# untitled.net
KiCad netlist of a schematic drawn in EAGLE
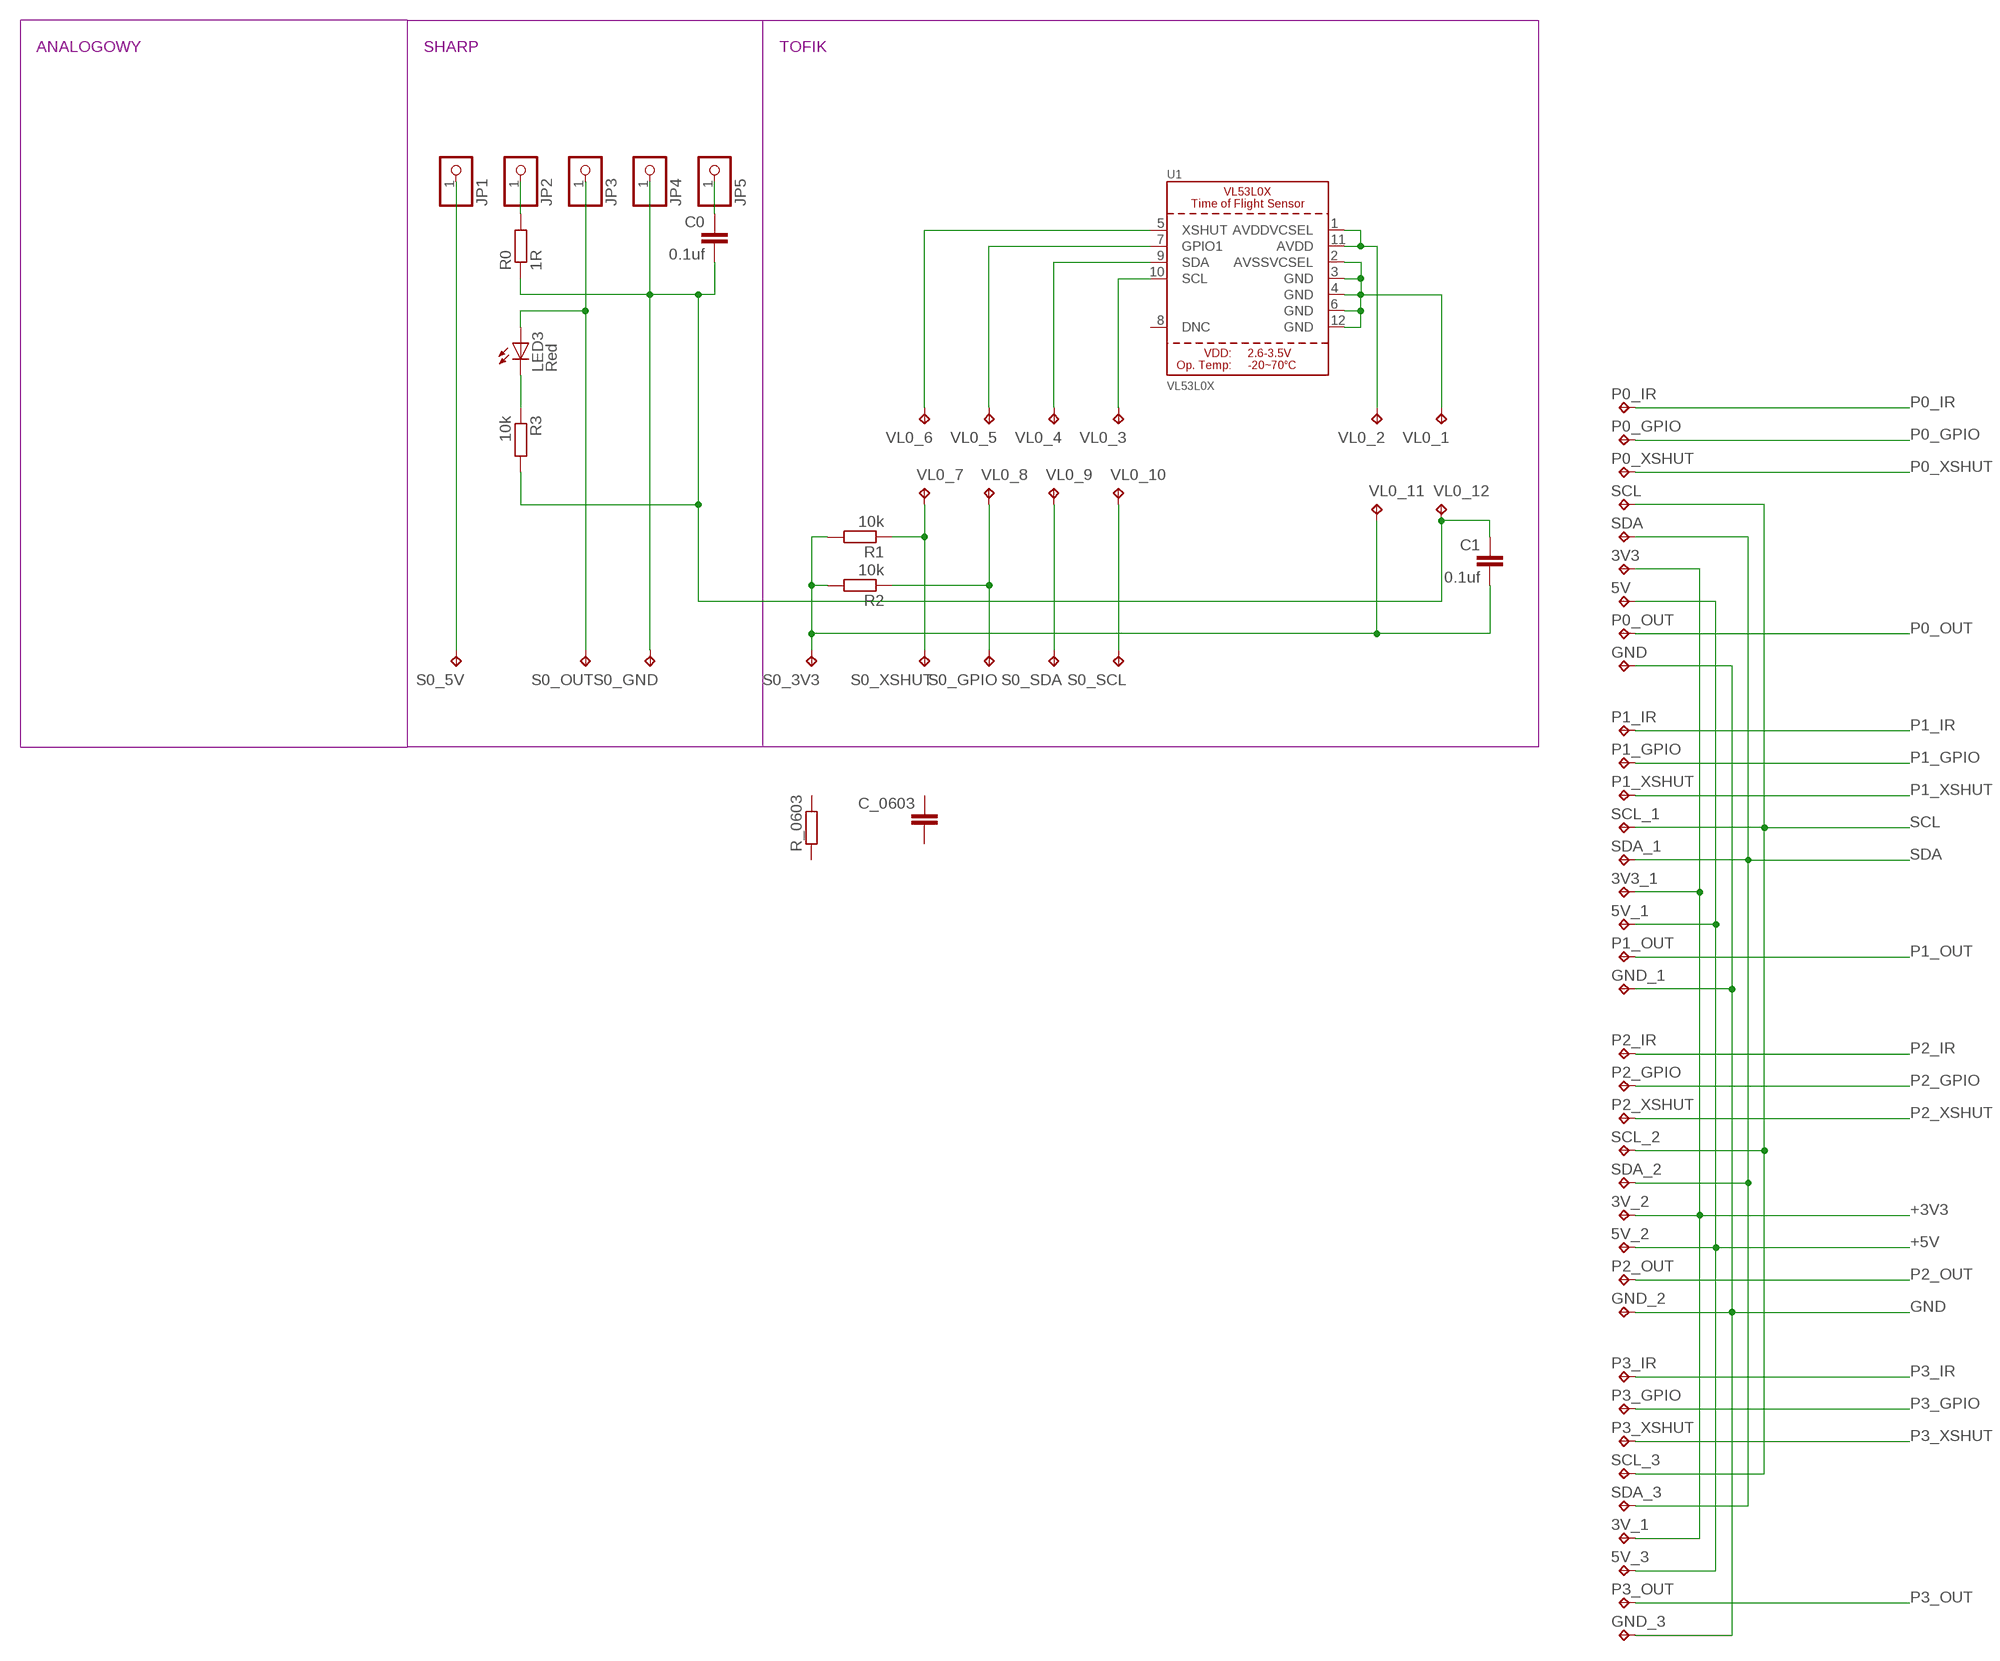
[diagram p0: schematic, sheet 1, part 1 of 2]
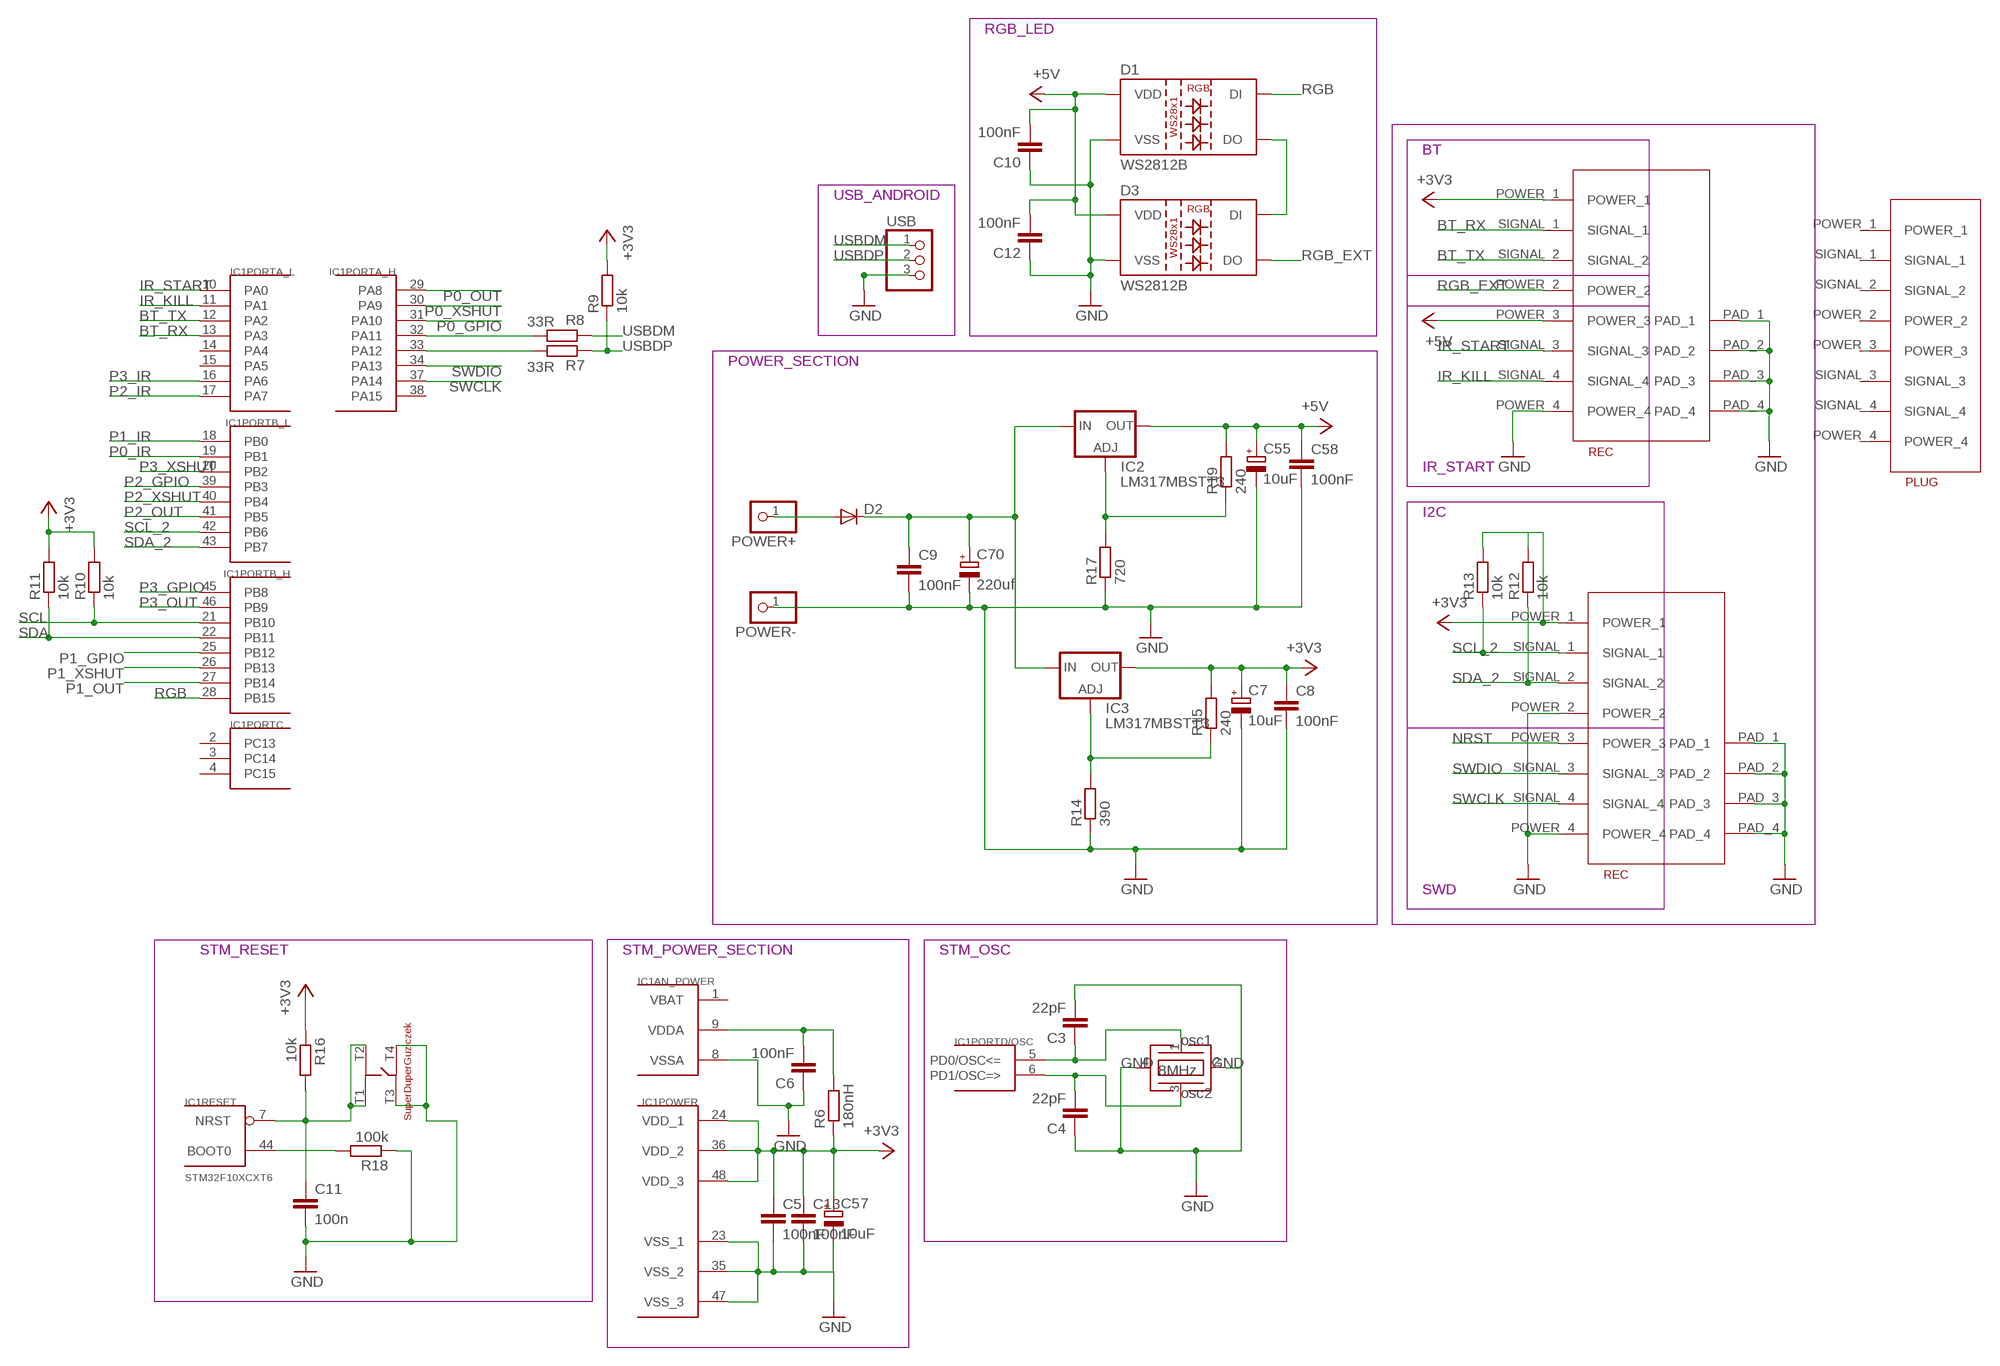
[diagram p1: schematic, sheet 1, part 2 of 2]

(export (version "E")
  (design (tool "Eeschema 10.0.6"))
  (components
    (comp (ref "3V3")
      (value "TPTP09SQ")
      (footprint "eagle-import:TP09SQ")
      (libsource (lib "eagle-import") (part "TPTP09SQ"))
    )
    (comp (ref "3V3_1")
      (value "TPTP09SQ")
      (footprint "eagle-import:TP09SQ")
      (libsource (lib "eagle-import") (part "TPTP09SQ"))
    )
    (comp (ref "3V_1")
      (value "TPTP09SQ")
      (footprint "eagle-import:TP09SQ")
      (libsource (lib "eagle-import") (part "TPTP09SQ"))
    )
    (comp (ref "3V_2")
      (value "TPTP09SQ")
      (footprint "eagle-import:TP09SQ")
      (libsource (lib "eagle-import") (part "TPTP09SQ"))
    )
    (comp (ref "5V")
      (value "TPTP09SQ")
      (footprint "eagle-import:TP09SQ")
      (libsource (lib "eagle-import") (part "TPTP09SQ"))
    )
    (comp (ref "5V_1")
      (value "TPTP09SQ")
      (footprint "eagle-import:TP09SQ")
      (libsource (lib "eagle-import") (part "TPTP09SQ"))
    )
    (comp (ref "5V_2")
      (value "TPTP09SQ")
      (footprint "eagle-import:TP09SQ")
      (libsource (lib "eagle-import") (part "TPTP09SQ"))
    )
    (comp (ref "5V_3")
      (value "TPTP09SQ")
      (footprint "eagle-import:TP09SQ")
      (libsource (lib "eagle-import") (part "TPTP09SQ"))
    )
    (comp (ref "C0")
      (value "0.1uf")
      (footprint "eagle-import:C0603")
      (libsource (lib "eagle-import") (part "C-EUC0603"))
    )
    (comp (ref "C1")
      (value "0.1uf")
      (footprint "eagle-import:C0603")
      (libsource (lib "eagle-import") (part "C-EUC0603"))
    )
    (comp (ref "C3")
      (value "22pF")
      (footprint "eagle-import:C0603")
      (libsource (lib "eagle-import") (part "C-EUC0603"))
    )
    (comp (ref "C4")
      (value "22pF")
      (footprint "eagle-import:C0603")
      (libsource (lib "eagle-import") (part "C-EUC0603"))
    )
    (comp (ref "C5")
      (value "100nF")
      (footprint "eagle-import:C0603")
      (libsource (lib "eagle-import") (part "C-EUC0603"))
    )
    (comp (ref "C6")
      (value "100nF")
      (footprint "eagle-import:C0603")
      (libsource (lib "eagle-import") (part "C-EUC0603"))
    )
    (comp (ref "C7")
      (value "10uF")
      (footprint "eagle-import:SMC_A")
      (libsource (lib "eagle-import") (part "CPOL-EUSMCA"))
    )
    (comp (ref "C8")
      (value "100nF")
      (footprint "eagle-import:C0603")
      (libsource (lib "eagle-import") (part "C-EUC0603"))
    )
    (comp (ref "C9")
      (value "100nF")
      (footprint "eagle-import:C0603")
      (libsource (lib "eagle-import") (part "C-EUC0603"))
    )
    (comp (ref "C10")
      (value "100nF")
      (footprint "eagle-import:C0603")
      (libsource (lib "eagle-import") (part "C-EUC0603"))
    )
    (comp (ref "C11")
      (value "100n")
      (footprint "eagle-import:C0603")
      (libsource (lib "eagle-import") (part "C-EUC0603"))
    )
    (comp (ref "C12")
      (value "100nF")
      (footprint "eagle-import:C0603")
      (libsource (lib "eagle-import") (part "C-EUC0603"))
    )
    (comp (ref "C13")
      (value "100nF")
      (footprint "eagle-import:C0603")
      (libsource (lib "eagle-import") (part "C-EUC0603"))
    )
    (comp (ref "C55")
      (value "10uF")
      (footprint "eagle-import:SMC_A")
      (libsource (lib "eagle-import") (part "CPOL-EUSMCA"))
    )
    (comp (ref "C57")
      (value "10uF")
      (footprint "eagle-import:SMC_A")
      (libsource (lib "eagle-import") (part "CPOL-EUSMCA"))
    )
    (comp (ref "C58")
      (value "100nF")
      (footprint "eagle-import:C0603")
      (libsource (lib "eagle-import") (part "C-EUC0603"))
    )
    (comp (ref "C70")
      (value "220uf")
      (footprint "eagle-import:150CLZ-0810")
      (libsource (lib "eagle-import") (part "CPOL-EU150CLZ-0810"))
    )
    (comp (ref "C_0603")
      (value "C-EUC0603")
      (footprint "eagle-import:C0603")
      (libsource (lib "eagle-import") (part "C-EUC0603"))
    )
    (comp (ref "D1")
      (value "WS2812B")
      (footprint "eagle-import:WS2812B")
      (libsource (lib "eagle-import") (part "WS2812B"))
    )
    (comp (ref "D2")
      (value "DIODE-DO214BA")
      (footprint "eagle-import:DO214BA")
      (libsource (lib "eagle-import") (part "DIODE-DO214BA"))
    )
    (comp (ref "D3")
      (value "WS2812B")
      (footprint "eagle-import:WS2812B")
      (libsource (lib "eagle-import") (part "WS2812B"))
    )
    (comp (ref "GND")
      (value "TPTP09SQ")
      (footprint "eagle-import:TP09SQ")
      (libsource (lib "eagle-import") (part "TPTP09SQ"))
    )
    (comp (ref "GND_1")
      (value "TPTP09SQ")
      (footprint "eagle-import:TP09SQ")
      (libsource (lib "eagle-import") (part "TPTP09SQ"))
    )
    (comp (ref "GND_2")
      (value "TPTP09SQ")
      (footprint "eagle-import:TP09SQ")
      (libsource (lib "eagle-import") (part "TPTP09SQ"))
    )
    (comp (ref "GND_3")
      (value "TPTP09SQ")
      (footprint "eagle-import:TP09SQ")
      (libsource (lib "eagle-import") (part "TPTP09SQ"))
    )
    (comp (ref "IC1")
      (value "STM32F10XCXT6")
      (footprint "eagle-import:TQFP48")
      (libsource (lib "eagle-import") (part "STM32F10XCXT6"))
    )
    (comp (ref "IC2")
      (value "LM317MBSTT3")
      (footprint "eagle-import:SOT223")
      (libsource (lib "eagle-import") (part "LM317?MBSTT3"))
    )
    (comp (ref "IC3")
      (value "LM317MBSTT3")
      (footprint "eagle-import:SOT223")
      (libsource (lib "eagle-import") (part "LM317?MBSTT3"))
    )
    (comp (ref "JP1")
      (value "PINHD-1X1")
      (footprint "eagle-import:1X01")
      (libsource (lib "eagle-import") (part "PINHD-1X1"))
    )
    (comp (ref "JP2")
      (value "PINHD-1X1")
      (footprint "eagle-import:1X01")
      (libsource (lib "eagle-import") (part "PINHD-1X1"))
    )
    (comp (ref "JP3")
      (value "PINHD-1X1")
      (footprint "eagle-import:1X01")
      (libsource (lib "eagle-import") (part "PINHD-1X1"))
    )
    (comp (ref "JP4")
      (value "PINHD-1X1")
      (footprint "eagle-import:1X01")
      (libsource (lib "eagle-import") (part "PINHD-1X1"))
    )
    (comp (ref "JP5")
      (value "PINHD-1X1")
      (footprint "eagle-import:1X01")
      (libsource (lib "eagle-import") (part "PINHD-1X1"))
    )
    (comp (ref "LED3")
      (value "Red")
      (footprint "eagle-import:SML0603")
      (libsource (lib "eagle-import") (part "LEDSML0603"))
    )
    (comp (ref "P0_GPIO")
      (value "TPTP09SQ")
      (footprint "eagle-import:TP09SQ")
      (libsource (lib "eagle-import") (part "TPTP09SQ"))
    )
    (comp (ref "P0_IR")
      (value "TPTP09SQ")
      (footprint "eagle-import:TP09SQ")
      (libsource (lib "eagle-import") (part "TPTP09SQ"))
    )
    (comp (ref "P0_OUT")
      (value "TPTP09SQ")
      (footprint "eagle-import:TP09SQ")
      (libsource (lib "eagle-import") (part "TPTP09SQ"))
    )
    (comp (ref "P0_XSHUT")
      (value "TPTP09SQ")
      (footprint "eagle-import:TP09SQ")
      (libsource (lib "eagle-import") (part "TPTP09SQ"))
    )
    (comp (ref "P1_GPIO")
      (value "TPTP09SQ")
      (footprint "eagle-import:TP09SQ")
      (libsource (lib "eagle-import") (part "TPTP09SQ"))
    )
    (comp (ref "P1_IR")
      (value "TPTP09SQ")
      (footprint "eagle-import:TP09SQ")
      (libsource (lib "eagle-import") (part "TPTP09SQ"))
    )
    (comp (ref "P1_OUT")
      (value "TPTP09SQ")
      (footprint "eagle-import:TP09SQ")
      (libsource (lib "eagle-import") (part "TPTP09SQ"))
    )
    (comp (ref "P1_XSHUT")
      (value "TPTP09SQ")
      (footprint "eagle-import:TP09SQ")
      (libsource (lib "eagle-import") (part "TPTP09SQ"))
    )
    (comp (ref "P2_GPIO")
      (value "TPTP09SQ")
      (footprint "eagle-import:TP09SQ")
      (libsource (lib "eagle-import") (part "TPTP09SQ"))
    )
    (comp (ref "P2_IR")
      (value "TPTP09SQ")
      (footprint "eagle-import:TP09SQ")
      (libsource (lib "eagle-import") (part "TPTP09SQ"))
    )
    (comp (ref "P2_OUT")
      (value "TPTP09SQ")
      (footprint "eagle-import:TP09SQ")
      (libsource (lib "eagle-import") (part "TPTP09SQ"))
    )
    (comp (ref "P2_XSHUT")
      (value "TPTP09SQ")
      (footprint "eagle-import:TP09SQ")
      (libsource (lib "eagle-import") (part "TPTP09SQ"))
    )
    (comp (ref "P3_GPIO")
      (value "TPTP09SQ")
      (footprint "eagle-import:TP09SQ")
      (libsource (lib "eagle-import") (part "TPTP09SQ"))
    )
    (comp (ref "P3_IR")
      (value "TPTP09SQ")
      (footprint "eagle-import:TP09SQ")
      (libsource (lib "eagle-import") (part "TPTP09SQ"))
    )
    (comp (ref "P3_OUT")
      (value "TPTP09SQ")
      (footprint "eagle-import:TP09SQ")
      (libsource (lib "eagle-import") (part "TPTP09SQ"))
    )
    (comp (ref "P3_XSHUT")
      (value "TPTP09SQ")
      (footprint "eagle-import:TP09SQ")
      (libsource (lib "eagle-import") (part "TPTP09SQ"))
    )
    (comp (ref "POWER+")
      (value "PINHD-1X1")
      (footprint "eagle-import:1X01")
      (libsource (lib "eagle-import") (part "PINHD-1X1"))
    )
    (comp (ref "POWER-")
      (value "PINHD-1X1")
      (footprint "eagle-import:1X01")
      (libsource (lib "eagle-import") (part "PINHD-1X1"))
    )
    (comp (ref "R0")
      (value "1R")
      (footprint "eagle-import:R0603")
      (libsource (lib "eagle-import") (part "R-EU_R0603"))
    )
    (comp (ref "R1")
      (value "10k")
      (footprint "eagle-import:R0603")
      (libsource (lib "eagle-import") (part "R-EU_R0603"))
    )
    (comp (ref "R2")
      (value "10k")
      (footprint "eagle-import:R0603")
      (libsource (lib "eagle-import") (part "R-EU_R0603"))
    )
    (comp (ref "R3")
      (value "10k")
      (footprint "eagle-import:R0603")
      (libsource (lib "eagle-import") (part "R-EU_R0603"))
    )
    (comp (ref "R6")
      (value "180nH")
      (footprint "eagle-import:R0603")
      (libsource (lib "eagle-import") (part "R-EU_R0603"))
    )
    (comp (ref "R7")
      (value "33R")
      (footprint "eagle-import:R0603")
      (libsource (lib "eagle-import") (part "R-EU_R0603"))
    )
    (comp (ref "R8")
      (value "33R")
      (footprint "eagle-import:R0603")
      (libsource (lib "eagle-import") (part "R-EU_R0603"))
    )
    (comp (ref "R9")
      (value "10k")
      (footprint "eagle-import:R0603")
      (libsource (lib "eagle-import") (part "R-EU_R0603"))
    )
    (comp (ref "R10")
      (value "10k")
      (footprint "eagle-import:R0603")
      (libsource (lib "eagle-import") (part "R-EU_R0603"))
    )
    (comp (ref "R11")
      (value "10k")
      (footprint "eagle-import:R0603")
      (libsource (lib "eagle-import") (part "R-EU_R0603"))
    )
    (comp (ref "R12")
      (value "10k")
      (footprint "eagle-import:R0603")
      (libsource (lib "eagle-import") (part "R-EU_R0603"))
    )
    (comp (ref "R13")
      (value "10k")
      (footprint "eagle-import:R0603")
      (libsource (lib "eagle-import") (part "R-EU_R0603"))
    )
    (comp (ref "R14")
      (value "390")
      (footprint "eagle-import:R0603")
      (libsource (lib "eagle-import") (part "R-EU_R0603"))
    )
    (comp (ref "R15")
      (value "240")
      (footprint "eagle-import:R0603")
      (libsource (lib "eagle-import") (part "R-EU_R0603"))
    )
    (comp (ref "R16")
      (value "10k")
      (footprint "eagle-import:R0603")
      (libsource (lib "eagle-import") (part "R-EU_R0603"))
    )
    (comp (ref "R17")
      (value "720")
      (footprint "eagle-import:R0603")
      (libsource (lib "eagle-import") (part "R-EU_R0603"))
    )
    (comp (ref "R18")
      (value "100k")
      (footprint "eagle-import:R0603")
      (libsource (lib "eagle-import") (part "R-EU_R0603"))
    )
    (comp (ref "R19")
      (value "240")
      (footprint "eagle-import:R0603")
      (libsource (lib "eagle-import") (part "R-EU_R0603"))
    )
    (comp (ref "R_0603")
      (value "R-EU_R0603")
      (footprint "eagle-import:R0603")
      (libsource (lib "eagle-import") (part "R-EU_R0603"))
    )
    (comp (ref "S0_3V3")
      (value "TPTP09SQ")
      (footprint "eagle-import:TP09SQ")
      (libsource (lib "eagle-import") (part "TPTP09SQ"))
    )
    (comp (ref "S0_5V")
      (value "TPTP09SQ")
      (footprint "eagle-import:TP09SQ")
      (libsource (lib "eagle-import") (part "TPTP09SQ"))
    )
    (comp (ref "S0_GND")
      (value "TPTP09SQ")
      (footprint "eagle-import:TP09SQ")
      (libsource (lib "eagle-import") (part "TPTP09SQ"))
    )
    (comp (ref "S0_GPIO")
      (value "TPTP09SQ")
      (footprint "eagle-import:TP09SQ")
      (libsource (lib "eagle-import") (part "TPTP09SQ"))
    )
    (comp (ref "S0_OUT")
      (value "TPTP09SQ")
      (footprint "eagle-import:TP09SQ")
      (libsource (lib "eagle-import") (part "TPTP09SQ"))
    )
    (comp (ref "S0_SCL")
      (value "TPTP09SQ")
      (footprint "eagle-import:TP09SQ")
      (libsource (lib "eagle-import") (part "TPTP09SQ"))
    )
    (comp (ref "S0_SDA")
      (value "TPTP09SQ")
      (footprint "eagle-import:TP09SQ")
      (libsource (lib "eagle-import") (part "TPTP09SQ"))
    )
    (comp (ref "S0_XSHUT")
      (value "TPTP09SQ")
      (footprint "eagle-import:TP09SQ")
      (libsource (lib "eagle-import") (part "TPTP09SQ"))
    )
    (comp (ref "SCL")
      (value "TPTP09SQ")
      (footprint "eagle-import:TP09SQ")
      (libsource (lib "eagle-import") (part "TPTP09SQ"))
    )
    (comp (ref "SCL_1")
      (value "TPTP09SQ")
      (footprint "eagle-import:TP09SQ")
      (libsource (lib "eagle-import") (part "TPTP09SQ"))
    )
    (comp (ref "SCL_2")
      (value "TPTP09SQ")
      (footprint "eagle-import:TP09SQ")
      (libsource (lib "eagle-import") (part "TPTP09SQ"))
    )
    (comp (ref "SCL_3")
      (value "TPTP09SQ")
      (footprint "eagle-import:TP09SQ")
      (libsource (lib "eagle-import") (part "TPTP09SQ"))
    )
    (comp (ref "SDA")
      (value "TPTP09SQ")
      (footprint "eagle-import:TP09SQ")
      (libsource (lib "eagle-import") (part "TPTP09SQ"))
    )
    (comp (ref "SDA_1")
      (value "TPTP09SQ")
      (footprint "eagle-import:TP09SQ")
      (libsource (lib "eagle-import") (part "TPTP09SQ"))
    )
    (comp (ref "SDA_2")
      (value "TPTP09SQ")
      (footprint "eagle-import:TP09SQ")
      (libsource (lib "eagle-import") (part "TPTP09SQ"))
    )
    (comp (ref "SDA_3")
      (value "TPTP09SQ")
      (footprint "eagle-import:TP09SQ")
      (libsource (lib "eagle-import") (part "TPTP09SQ"))
    )
    (comp (ref "U$1")
      (value "MOLEG_REC_8X0.4MM")
      (footprint "eagle-import:REC")
      (libsource (lib "eagle-import") (part "MOLEG_REC_8X0.4MM"))
    )
    (comp (ref "U$2")
      (value "MOLEX_PLUG_8X0.4MM")
      (footprint "eagle-import:PLUG")
      (libsource (lib "eagle-import") (part "MOLEX_PLUG_8X0.4MM"))
    )
    (comp (ref "U$3")
      (value "MOLEG_REC_8X0.4MM")
      (footprint "eagle-import:REC")
      (libsource (lib "eagle-import") (part "MOLEG_REC_8X0.4MM"))
    )
    (comp (ref "U$27")
      (value "SUPER_DUPER_GUZICZEK")
      (footprint "eagle-import:SUPER_DUPER_GUZICZEK")
      (libsource (lib "eagle-import") (part "SUPER_DUPER_GUZICZEK"))
    )
    (comp (ref "U$35")
      (value "8MHZ")
      (footprint "eagle-import:SMD")
      (libsource (lib "eagle-import") (part "8MHZ"))
    )
    (comp (ref "U1")
      (value "VL53L0X")
      (footprint "eagle-import:LGA12_ST")
      (libsource (lib "eagle-import") (part "VL53L0X"))
    )
    (comp (ref "USB")
      (value "PINHD-1X3")
      (footprint "eagle-import:1X03")
      (libsource (lib "eagle-import") (part "PINHD-1X3"))
    )
    (comp (ref "VL0_1")
      (value "TPTP09SQ")
      (footprint "eagle-import:TP09SQ")
      (libsource (lib "eagle-import") (part "TPTP09SQ"))
    )
    (comp (ref "VL0_2")
      (value "TPTP09SQ")
      (footprint "eagle-import:TP09SQ")
      (libsource (lib "eagle-import") (part "TPTP09SQ"))
    )
    (comp (ref "VL0_3")
      (value "TPTP09SQ")
      (footprint "eagle-import:TP09SQ")
      (libsource (lib "eagle-import") (part "TPTP09SQ"))
    )
    (comp (ref "VL0_4")
      (value "TPTP09SQ")
      (footprint "eagle-import:TP09SQ")
      (libsource (lib "eagle-import") (part "TPTP09SQ"))
    )
    (comp (ref "VL0_5")
      (value "TPTP09SQ")
      (footprint "eagle-import:TP09SQ")
      (libsource (lib "eagle-import") (part "TPTP09SQ"))
    )
    (comp (ref "VL0_6")
      (value "TPTP09SQ")
      (footprint "eagle-import:TP09SQ")
      (libsource (lib "eagle-import") (part "TPTP09SQ"))
    )
    (comp (ref "VL0_7")
      (value "TPTP09SQ")
      (footprint "eagle-import:TP09SQ")
      (libsource (lib "eagle-import") (part "TPTP09SQ"))
    )
    (comp (ref "VL0_8")
      (value "TPTP09SQ")
      (footprint "eagle-import:TP09SQ")
      (libsource (lib "eagle-import") (part "TPTP09SQ"))
    )
    (comp (ref "VL0_9")
      (value "TPTP09SQ")
      (footprint "eagle-import:TP09SQ")
      (libsource (lib "eagle-import") (part "TPTP09SQ"))
    )
    (comp (ref "VL0_10")
      (value "TPTP09SQ")
      (footprint "eagle-import:TP09SQ")
      (libsource (lib "eagle-import") (part "TPTP09SQ"))
    )
    (comp (ref "VL0_11")
      (value "TPTP09SQ")
      (footprint "eagle-import:TP09SQ")
      (libsource (lib "eagle-import") (part "TPTP09SQ"))
    )
    (comp (ref "VL0_12")
      (value "TPTP09SQ")
      (footprint "eagle-import:TP09SQ")
      (libsource (lib "eagle-import") (part "TPTP09SQ"))
    )
  )
  (nets
    (net (code "1") (name "+3V3") (class "Default")
      (node (ref "3V3") (pin "TP") (pinfunction "TP_TP") (pintype "input"))
      (node (ref "3V3_1") (pin "TP") (pinfunction "TP_TP") (pintype "input"))
      (node (ref "3V_1") (pin "TP") (pinfunction "TP_TP") (pintype "input"))
      (node (ref "3V_2") (pin "TP") (pinfunction "TP_TP") (pintype "input"))
      (node (ref "C13") (pin "1") (pinfunction "1_1") (pintype "passive"))
      (node (ref "C5") (pin "1") (pinfunction "1_1") (pintype "passive"))
      (node (ref "C57") (pin "+") (pinfunction "+_+") (pintype "passive"))
      (node (ref "C7") (pin "+") (pinfunction "+_+") (pintype "passive"))
      (node (ref "C8") (pin "1") (pinfunction "1_1") (pintype "passive"))
      (node (ref "IC1") (pin "24") (pinfunction "VDD_1_24") (pintype "power_in"))
      (node (ref "IC1") (pin "36") (pinfunction "VDD_2_36") (pintype "power_in"))
      (node (ref "IC1") (pin "48") (pinfunction "VDD_3_48") (pintype "power_in"))
      (node (ref "IC3") (pin "4") (pinfunction "OUT_4") (pintype "passive"))
      (node (ref "R10") (pin "2") (pinfunction "2_2") (pintype "passive"))
      (node (ref "R11") (pin "2") (pinfunction "2_2") (pintype "passive"))
      (node (ref "R12") (pin "2") (pinfunction "2_2") (pintype "passive"))
      (node (ref "R13") (pin "2") (pinfunction "2_2") (pintype "passive"))
      (node (ref "R15") (pin "2") (pinfunction "2_2") (pintype "passive"))
      (node (ref "R16") (pin "1") (pinfunction "1_1") (pintype "passive"))
      (node (ref "R6") (pin "1") (pinfunction "1_1") (pintype "passive"))
      (node (ref "R9") (pin "2") (pinfunction "2_2") (pintype "passive"))
      (node (ref "U$1") (pin "POWER_1") (pinfunction "POWER_1_POWER_1") (pintype "bidirectional"))
      (node (ref "U$3") (pin "POWER_1") (pinfunction "POWER_1_POWER_1") (pintype "bidirectional"))
    )
    (net (code "2") (name "+5V") (class "Default")
      (node (ref "5V") (pin "TP") (pinfunction "TP_TP") (pintype "input"))
      (node (ref "5V_1") (pin "TP") (pinfunction "TP_TP") (pintype "input"))
      (node (ref "5V_2") (pin "TP") (pinfunction "TP_TP") (pintype "input"))
      (node (ref "5V_3") (pin "TP") (pinfunction "TP_TP") (pintype "input"))
      (node (ref "C10") (pin "2") (pinfunction "2_2") (pintype "passive"))
      (node (ref "C12") (pin "2") (pinfunction "2_2") (pintype "passive"))
      (node (ref "C55") (pin "+") (pinfunction "+_+") (pintype "passive"))
      (node (ref "C58") (pin "1") (pinfunction "1_1") (pintype "passive"))
      (node (ref "D1") (pin "1") (pinfunction "VDD_1") (pintype "bidirectional"))
      (node (ref "D3") (pin "1") (pinfunction "VDD_1") (pintype "bidirectional"))
      (node (ref "IC2") (pin "4") (pinfunction "OUT_4") (pintype "passive"))
      (node (ref "R19") (pin "2") (pinfunction "2_2") (pintype "passive"))
      (node (ref "U$1") (pin "POWER_3") (pinfunction "POWER_3_POWER_3") (pintype "bidirectional"))
    )
    (net (code "3") (name "/BT_RX") (class "Default")
      (node (ref "IC1") (pin "13") (pinfunction "PA3_13") (pintype "bidirectional"))
      (node (ref "U$1") (pin "SIGNAL_1") (pinfunction "SIGNAL_1_SIGNAL_1") (pintype "bidirectional"))
    )
    (net (code "4") (name "/BT_TX") (class "Default")
      (node (ref "IC1") (pin "12") (pinfunction "PA2_12") (pintype "bidirectional"))
      (node (ref "U$1") (pin "SIGNAL_2") (pinfunction "SIGNAL_2_SIGNAL_2") (pintype "bidirectional"))
    )
    (net (code "5") (name "/IR_KILL") (class "Default")
      (node (ref "IC1") (pin "11") (pinfunction "PA1_11") (pintype "bidirectional"))
      (node (ref "U$1") (pin "SIGNAL_4") (pinfunction "SIGNAL_4_SIGNAL_4") (pintype "bidirectional"))
    )
    (net (code "6") (name "/IR_START") (class "Default")
      (node (ref "IC1") (pin "10") (pinfunction "PA0_10") (pintype "bidirectional"))
      (node (ref "U$1") (pin "SIGNAL_3") (pinfunction "SIGNAL_3_SIGNAL_3") (pintype "bidirectional"))
    )
    (net (code "7") (name "/NRST") (class "Default")
      (node (ref "C11") (pin "1") (pinfunction "1_1") (pintype "passive"))
      (node (ref "IC1") (pin "7") (pinfunction "NRST_7") (pintype "input"))
      (node (ref "R16") (pin "2") (pinfunction "2_2") (pintype "passive"))
      (node (ref "U$27") (pin "T1") (pinfunction "T1_T1") (pintype "bidirectional"))
      (node (ref "U$27") (pin "T2") (pinfunction "T2_T2") (pintype "bidirectional"))
      (node (ref "U$3") (pin "POWER_3") (pinfunction "POWER_3_POWER_3") (pintype "bidirectional"))
    )
    (net (code "8") (name "/P0_GPIO") (class "Default")
      (node (ref "IC1") (pin "31") (pinfunction "PA10_31") (pintype "bidirectional"))
      (node (ref "P0_GPIO") (pin "TP") (pinfunction "TP_TP") (pintype "input"))
    )
    (net (code "9") (name "/P0_IR") (class "Default")
      (node (ref "IC1") (pin "19") (pinfunction "PB1_19") (pintype "bidirectional"))
      (node (ref "P0_IR") (pin "TP") (pinfunction "TP_TP") (pintype "input"))
    )
    (net (code "10") (name "/P0_OUT") (class "Default")
      (node (ref "IC1") (pin "29") (pinfunction "PA8_29") (pintype "bidirectional"))
      (node (ref "P0_OUT") (pin "TP") (pinfunction "TP_TP") (pintype "input"))
    )
    (net (code "11") (name "/P0_XSHUT") (class "Default")
      (node (ref "IC1") (pin "30") (pinfunction "PA9_30") (pintype "bidirectional"))
      (node (ref "P0_XSHUT") (pin "TP") (pinfunction "TP_TP") (pintype "input"))
    )
    (net (code "12") (name "/P1_GPIO") (class "Default")
      (node (ref "IC1") (pin "25") (pinfunction "PB12_25") (pintype "bidirectional"))
      (node (ref "P1_GPIO") (pin "TP") (pinfunction "TP_TP") (pintype "input"))
    )
    (net (code "13") (name "/P1_IR") (class "Default")
      (node (ref "IC1") (pin "18") (pinfunction "PB0_18") (pintype "bidirectional"))
      (node (ref "P1_IR") (pin "TP") (pinfunction "TP_TP") (pintype "input"))
    )
    (net (code "14") (name "/P1_OUT") (class "Default")
      (node (ref "IC1") (pin "27") (pinfunction "PB14_27") (pintype "bidirectional"))
      (node (ref "P1_OUT") (pin "TP") (pinfunction "TP_TP") (pintype "input"))
    )
    (net (code "15") (name "/P1_XSHUT") (class "Default")
      (node (ref "IC1") (pin "26") (pinfunction "PB13_26") (pintype "bidirectional"))
      (node (ref "P1_XSHUT") (pin "TP") (pinfunction "TP_TP") (pintype "input"))
    )
    (net (code "16") (name "/P2_GPIO") (class "Default")
      (node (ref "IC1") (pin "39") (pinfunction "PB3_39") (pintype "bidirectional"))
      (node (ref "P2_GPIO") (pin "TP") (pinfunction "TP_TP") (pintype "input"))
    )
    (net (code "17") (name "/P2_IR") (class "Default")
      (node (ref "IC1") (pin "17") (pinfunction "PA7_17") (pintype "bidirectional"))
      (node (ref "P2_IR") (pin "TP") (pinfunction "TP_TP") (pintype "input"))
    )
    (net (code "18") (name "/P2_OUT") (class "Default")
      (node (ref "IC1") (pin "41") (pinfunction "PB5_41") (pintype "bidirectional"))
      (node (ref "P2_OUT") (pin "TP") (pinfunction "TP_TP") (pintype "input"))
    )
    (net (code "19") (name "/P2_XSHUT") (class "Default")
      (node (ref "IC1") (pin "40") (pinfunction "PB4_40") (pintype "bidirectional"))
      (node (ref "P2_XSHUT") (pin "TP") (pinfunction "TP_TP") (pintype "input"))
    )
    (net (code "20") (name "/P3_GPIO") (class "Default")
      (node (ref "IC1") (pin "45") (pinfunction "PB8_45") (pintype "bidirectional"))
      (node (ref "P3_GPIO") (pin "TP") (pinfunction "TP_TP") (pintype "input"))
    )
    (net (code "21") (name "/P3_IR") (class "Default")
      (node (ref "IC1") (pin "16") (pinfunction "PA6_16") (pintype "bidirectional"))
      (node (ref "P3_IR") (pin "TP") (pinfunction "TP_TP") (pintype "input"))
    )
    (net (code "22") (name "/P3_OUT") (class "Default")
      (node (ref "IC1") (pin "46") (pinfunction "PB9_46") (pintype "bidirectional"))
      (node (ref "P3_OUT") (pin "TP") (pinfunction "TP_TP") (pintype "input"))
    )
    (net (code "23") (name "/P3_XSHUT") (class "Default")
      (node (ref "IC1") (pin "20") (pinfunction "PB2_20") (pintype "bidirectional"))
      (node (ref "P3_XSHUT") (pin "TP") (pinfunction "TP_TP") (pintype "input"))
    )
    (net (code "24") (name "/RGB") (class "Default")
      (node (ref "D1") (pin "4") (pinfunction "DI_4") (pintype "bidirectional"))
      (node (ref "IC1") (pin "28") (pinfunction "PB15_28") (pintype "bidirectional"))
    )
    (net (code "25") (name "/RGB_EXT") (class "Default")
      (node (ref "D3") (pin "2") (pinfunction "DO_2") (pintype "bidirectional"))
      (node (ref "U$1") (pin "POWER_2") (pinfunction "POWER_2_POWER_2") (pintype "bidirectional"))
    )
    (net (code "26") (name "/SCL") (class "Default")
      (node (ref "IC1") (pin "21") (pinfunction "PB10_21") (pintype "bidirectional"))
      (node (ref "R10") (pin "1") (pinfunction "1_1") (pintype "passive"))
      (node (ref "SCL") (pin "TP") (pinfunction "TP_TP") (pintype "input"))
      (node (ref "SCL_1") (pin "TP") (pinfunction "TP_TP") (pintype "input"))
      (node (ref "SCL_2") (pin "TP") (pinfunction "TP_TP") (pintype "input"))
      (node (ref "SCL_3") (pin "TP") (pinfunction "TP_TP") (pintype "input"))
    )
    (net (code "27") (name "/SCL_2") (class "Default")
      (node (ref "IC1") (pin "42") (pinfunction "PB6_42") (pintype "bidirectional"))
      (node (ref "R13") (pin "1") (pinfunction "1_1") (pintype "passive"))
      (node (ref "U$3") (pin "SIGNAL_1") (pinfunction "SIGNAL_1_SIGNAL_1") (pintype "bidirectional"))
    )
    (net (code "28") (name "/SDA") (class "Default")
      (node (ref "IC1") (pin "22") (pinfunction "PB11_22") (pintype "bidirectional"))
      (node (ref "R11") (pin "1") (pinfunction "1_1") (pintype "passive"))
      (node (ref "SDA") (pin "TP") (pinfunction "TP_TP") (pintype "input"))
      (node (ref "SDA_1") (pin "TP") (pinfunction "TP_TP") (pintype "input"))
      (node (ref "SDA_2") (pin "TP") (pinfunction "TP_TP") (pintype "input"))
      (node (ref "SDA_3") (pin "TP") (pinfunction "TP_TP") (pintype "input"))
    )
    (net (code "29") (name "/SDA_2") (class "Default")
      (node (ref "IC1") (pin "43") (pinfunction "PB7_43") (pintype "bidirectional"))
      (node (ref "R12") (pin "1") (pinfunction "1_1") (pintype "passive"))
      (node (ref "U$3") (pin "SIGNAL_2") (pinfunction "SIGNAL_2_SIGNAL_2") (pintype "bidirectional"))
    )
    (net (code "30") (name "/SWCLK") (class "Default")
      (node (ref "IC1") (pin "37") (pinfunction "PA14_37") (pintype "bidirectional"))
      (node (ref "U$3") (pin "SIGNAL_4") (pinfunction "SIGNAL_4_SIGNAL_4") (pintype "bidirectional"))
    )
    (net (code "31") (name "/SWDIO") (class "Default")
      (node (ref "IC1") (pin "34") (pinfunction "PA13_34") (pintype "bidirectional"))
      (node (ref "U$3") (pin "SIGNAL_3") (pinfunction "SIGNAL_3_SIGNAL_3") (pintype "bidirectional"))
    )
    (net (code "32") (name "/USBDM") (class "Default")
      (node (ref "R8") (pin "1") (pinfunction "1_1") (pintype "passive"))
      (node (ref "USB") (pin "1") (pinfunction "1_1") (pintype "passive"))
    )
    (net (code "33") (name "/USBDP") (class "Default")
      (node (ref "R7") (pin "1") (pinfunction "1_1") (pintype "passive"))
      (node (ref "R9") (pin "1") (pinfunction "1_1") (pintype "passive"))
      (node (ref "USB") (pin "2") (pinfunction "2_2") (pintype "passive"))
    )
    (net (code "34") (name "/VBAT") (class "Default")
      (node (ref "IC1") (pin "1") (pinfunction "VBAT_1") (pintype "power_in"))
    )
    (net (code "35") (name "GND") (class "Default")
      (node (ref "C10") (pin "1") (pinfunction "1_1") (pintype "passive"))
      (node (ref "C11") (pin "2") (pinfunction "2_2") (pintype "passive"))
      (node (ref "C12") (pin "1") (pinfunction "1_1") (pintype "passive"))
      (node (ref "C13") (pin "2") (pinfunction "2_2") (pintype "passive"))
      (node (ref "C3") (pin "2") (pinfunction "2_2") (pintype "passive"))
      (node (ref "C4") (pin "1") (pinfunction "1_1") (pintype "passive"))
      (node (ref "C5") (pin "2") (pinfunction "2_2") (pintype "passive"))
      (node (ref "C55") (pin "-") (pinfunction "-_-") (pintype "passive"))
      (node (ref "C57") (pin "-") (pinfunction "-_-") (pintype "passive"))
      (node (ref "C58") (pin "2") (pinfunction "2_2") (pintype "passive"))
      (node (ref "C6") (pin "1") (pinfunction "1_1") (pintype "passive"))
      (node (ref "C7") (pin "-") (pinfunction "-_-") (pintype "passive"))
      (node (ref "C70") (pin "-") (pinfunction "-_-") (pintype "passive"))
      (node (ref "C8") (pin "2") (pinfunction "2_2") (pintype "passive"))
      (node (ref "C9") (pin "2") (pinfunction "2_2") (pintype "passive"))
      (node (ref "D1") (pin "3") (pinfunction "VSS_3") (pintype "bidirectional"))
      (node (ref "D3") (pin "3") (pinfunction "VSS_3") (pintype "bidirectional"))
      (node (ref "GND") (pin "TP") (pinfunction "TP_TP") (pintype "input"))
      (node (ref "GND_1") (pin "TP") (pinfunction "TP_TP") (pintype "input"))
      (node (ref "GND_2") (pin "TP") (pinfunction "TP_TP") (pintype "input"))
      (node (ref "GND_3") (pin "TP") (pinfunction "TP_TP") (pintype "input"))
      (node (ref "IC1") (pin "23") (pinfunction "VSS_1_23") (pintype "power_in"))
      (node (ref "IC1") (pin "35") (pinfunction "VSS_2_35") (pintype "power_in"))
      (node (ref "IC1") (pin "47") (pinfunction "VSS_3_47") (pintype "power_in"))
      (node (ref "IC1") (pin "8") (pinfunction "VSSA_8") (pintype "power_in"))
      (node (ref "POWER-") (pin "1") (pinfunction "1_1") (pintype "passive"))
      (node (ref "R14") (pin "1") (pinfunction "1_1") (pintype "passive"))
      (node (ref "R17") (pin "1") (pinfunction "1_1") (pintype "passive"))
      (node (ref "R18") (pin "1") (pinfunction "1_1") (pintype "passive"))
      (node (ref "U$1") (pin "PAD_1") (pinfunction "PAD_1_PAD_1") (pintype "bidirectional"))
      (node (ref "U$1") (pin "PAD_2") (pinfunction "PAD_2_PAD_2") (pintype "bidirectional"))
      (node (ref "U$1") (pin "PAD_3") (pinfunction "PAD_3_PAD_3") (pintype "bidirectional"))
      (node (ref "U$1") (pin "PAD_4") (pinfunction "PAD_4_PAD_4") (pintype "bidirectional"))
      (node (ref "U$1") (pin "POWER_4") (pinfunction "POWER_4_POWER_4") (pintype "bidirectional"))
      (node (ref "U$27") (pin "T3") (pinfunction "T3_T3") (pintype "bidirectional"))
      (node (ref "U$27") (pin "T4") (pinfunction "T4_T4") (pintype "bidirectional"))
      (node (ref "U$3") (pin "PAD_1") (pinfunction "PAD_1_PAD_1") (pintype "bidirectional"))
      (node (ref "U$3") (pin "PAD_2") (pinfunction "PAD_2_PAD_2") (pintype "bidirectional"))
      (node (ref "U$3") (pin "PAD_3") (pinfunction "PAD_3_PAD_3") (pintype "bidirectional"))
      (node (ref "U$3") (pin "PAD_4") (pinfunction "PAD_4_PAD_4") (pintype "bidirectional"))
      (node (ref "U$3") (pin "POWER_2") (pinfunction "POWER_2_POWER_2") (pintype "bidirectional"))
      (node (ref "U$3") (pin "POWER_4") (pinfunction "POWER_4_POWER_4") (pintype "bidirectional"))
      (node (ref "U$35") (pin "2") (pinfunction "GND2_2") (pintype "bidirectional"))
      (node (ref "U$35") (pin "4") (pinfunction "GND1_4") (pintype "bidirectional"))
      (node (ref "USB") (pin "3") (pinfunction "3_3") (pintype "passive"))
    )
    (net (code "36") (name "Net-(C0-Pad1)") (class "Default")
      (node (ref "C0") (pin "1") (pinfunction "1_1") (pintype "passive"))
      (node (ref "JP5") (pin "1") (pinfunction "1_1") (pintype "passive"))
    )
    (net (code "37") (name "Net-(C0-Pad2)") (class "Default")
      (node (ref "C0") (pin "2") (pinfunction "2_2") (pintype "passive"))
      (node (ref "C1") (pin "1") (pinfunction "1_1") (pintype "passive"))
      (node (ref "JP4") (pin "1") (pinfunction "1_1") (pintype "passive"))
      (node (ref "R0") (pin "1") (pinfunction "1_1") (pintype "passive"))
      (node (ref "R3") (pin "2") (pinfunction "2_2") (pintype "passive"))
      (node (ref "S0_GND") (pin "TP") (pinfunction "TP_TP") (pintype "input"))
      (node (ref "VL0_12") (pin "TP") (pinfunction "TP_TP") (pintype "input"))
    )
    (net (code "38") (name "Net-(C1-Pad2)") (class "Default")
      (node (ref "C1") (pin "2") (pinfunction "2_2") (pintype "passive"))
      (node (ref "R1") (pin "2") (pinfunction "2_2") (pintype "passive"))
      (node (ref "R2") (pin "2") (pinfunction "2_2") (pintype "passive"))
      (node (ref "S0_3V3") (pin "TP") (pinfunction "TP_TP") (pintype "input"))
      (node (ref "VL0_11") (pin "TP") (pinfunction "TP_TP") (pintype "input"))
    )
    (net (code "39") (name "Net-(D1-DO)") (class "Default")
      (node (ref "D1") (pin "2") (pinfunction "DO_2") (pintype "bidirectional"))
      (node (ref "D3") (pin "4") (pinfunction "DI_4") (pintype "bidirectional"))
    )
    (net (code "40") (name "Net-(D2-PadA)") (class "Default")
      (node (ref "D2") (pin "A") (pinfunction "A_A") (pintype "passive"))
      (node (ref "POWER+") (pin "1") (pinfunction "1_1") (pintype "passive"))
    )
    (net (code "41") (name "Net-(IC1A-VDDA)") (class "Default")
      (node (ref "C6") (pin "2") (pinfunction "2_2") (pintype "passive"))
      (node (ref "IC1") (pin "9") (pinfunction "VDDA_9") (pintype "power_in"))
      (node (ref "R6") (pin "2") (pinfunction "2_2") (pintype "passive"))
    )
    (net (code "42") (name "Net-(IC1B-PA11)") (class "Default")
      (node (ref "IC1") (pin "32") (pinfunction "PA11_32") (pintype "bidirectional"))
      (node (ref "R8") (pin "2") (pinfunction "2_2") (pintype "passive"))
    )
    (net (code "43") (name "Net-(IC1B-PA12)") (class "Default")
      (node (ref "IC1") (pin "33") (pinfunction "PA12_33") (pintype "bidirectional"))
      (node (ref "R7") (pin "2") (pinfunction "2_2") (pintype "passive"))
    )
    (net (code "44") (name "Net-(IC1G-PD0{slash}OSC<=)") (class "Default")
      (node (ref "C3") (pin "1") (pinfunction "1_1") (pintype "passive"))
      (node (ref "IC1") (pin "5") (pinfunction "PD0/OSC<=_5") (pintype "bidirectional"))
      (node (ref "U$35") (pin "1") (pinfunction "1_1") (pintype "bidirectional"))
    )
    (net (code "45") (name "Net-(IC1G-PD1{slash}OSC=>)") (class "Default")
      (node (ref "C4") (pin "2") (pinfunction "2_2") (pintype "passive"))
      (node (ref "IC1") (pin "6") (pinfunction "PD1/OSC=>_6") (pintype "bidirectional"))
      (node (ref "U$35") (pin "3") (pinfunction "2_3") (pintype "bidirectional"))
    )
    (net (code "46") (name "Net-(IC1I-BOOT0)") (class "Default")
      (node (ref "IC1") (pin "44") (pinfunction "BOOT0_44") (pintype "input"))
      (node (ref "R18") (pin "2") (pinfunction "2_2") (pintype "passive"))
    )
    (net (code "47") (name "Net-(IC2-ADJ)") (class "Default")
      (node (ref "IC2") (pin "1") (pinfunction "ADJ_1") (pintype "input"))
      (node (ref "R17") (pin "2") (pinfunction "2_2") (pintype "passive"))
      (node (ref "R19") (pin "1") (pinfunction "1_1") (pintype "passive"))
    )
    (net (code "48") (name "Net-(IC2-IN)") (class "Default")
      (node (ref "C70") (pin "+") (pinfunction "+_+") (pintype "passive"))
      (node (ref "C9") (pin "1") (pinfunction "1_1") (pintype "passive"))
      (node (ref "D2") (pin "C") (pinfunction "C_C") (pintype "passive"))
      (node (ref "IC2") (pin "3") (pinfunction "IN_3") (pintype "input"))
      (node (ref "IC3") (pin "3") (pinfunction "IN_3") (pintype "input"))
    )
    (net (code "49") (name "Net-(IC3-ADJ)") (class "Default")
      (node (ref "IC3") (pin "1") (pinfunction "ADJ_1") (pintype "input"))
      (node (ref "R14") (pin "2") (pinfunction "2_2") (pintype "passive"))
      (node (ref "R15") (pin "1") (pinfunction "1_1") (pintype "passive"))
    )
    (net (code "50") (name "Net-(JP1-Pad1)") (class "Default")
      (node (ref "JP1") (pin "1") (pinfunction "1_1") (pintype "passive"))
      (node (ref "S0_5V") (pin "TP") (pinfunction "TP_TP") (pintype "input"))
    )
    (net (code "51") (name "Net-(JP2-Pad1)") (class "Default")
      (node (ref "JP2") (pin "1") (pinfunction "1_1") (pintype "passive"))
      (node (ref "R0") (pin "2") (pinfunction "2_2") (pintype "passive"))
    )
    (net (code "52") (name "Net-(JP3-Pad1)") (class "Default")
      (node (ref "JP3") (pin "1") (pinfunction "1_1") (pintype "passive"))
      (node (ref "LED3") (pin "A") (pinfunction "A_A") (pintype "passive"))
      (node (ref "S0_OUT") (pin "TP") (pinfunction "TP_TP") (pintype "input"))
    )
    (net (code "53") (name "Net-(LED3-PadC)") (class "Default")
      (node (ref "LED3") (pin "C") (pinfunction "C_C") (pintype "passive"))
      (node (ref "R3") (pin "1") (pinfunction "1_1") (pintype "passive"))
    )
    (net (code "54") (name "Net-(R1-Pad1)") (class "Default")
      (node (ref "R1") (pin "1") (pinfunction "1_1") (pintype "passive"))
      (node (ref "S0_XSHUT") (pin "TP") (pinfunction "TP_TP") (pintype "input"))
      (node (ref "VL0_7") (pin "TP") (pinfunction "TP_TP") (pintype "input"))
    )
    (net (code "55") (name "Net-(R2-Pad1)") (class "Default")
      (node (ref "R2") (pin "1") (pinfunction "1_1") (pintype "passive"))
      (node (ref "S0_GPIO") (pin "TP") (pinfunction "TP_TP") (pintype "input"))
      (node (ref "VL0_8") (pin "TP") (pinfunction "TP_TP") (pintype "input"))
    )
    (net (code "56") (name "Net-(S0_SCL-PadTP)") (class "Default")
      (node (ref "S0_SCL") (pin "TP") (pinfunction "TP_TP") (pintype "input"))
      (node (ref "VL0_10") (pin "TP") (pinfunction "TP_TP") (pintype "input"))
    )
    (net (code "57") (name "Net-(S0_SDA-PadTP)") (class "Default")
      (node (ref "S0_SDA") (pin "TP") (pinfunction "TP_TP") (pintype "input"))
      (node (ref "VL0_9") (pin "TP") (pinfunction "TP_TP") (pintype "input"))
    )
    (net (code "58") (name "Net-(U1-AVDD)") (class "Default")
      (node (ref "U1") (pin "1") (pinfunction "AVDDVCSEL_1") (pintype "power_in"))
      (node (ref "U1") (pin "11") (pinfunction "AVDD_11") (pintype "power_in"))
      (node (ref "VL0_2") (pin "TP") (pinfunction "TP_TP") (pintype "input"))
    )
    (net (code "59") (name "Net-(U1-AVSSVCSEL)") (class "Default")
      (node (ref "U1") (pin "12") (pinfunction "GND_12") (pintype "power_in"))
      (node (ref "U1") (pin "2") (pinfunction "AVSSVCSEL_2") (pintype "power_in"))
      (node (ref "U1") (pin "3") (pinfunction "GND_3") (pintype "power_in"))
      (node (ref "U1") (pin "4") (pinfunction "GND_4") (pintype "power_in"))
      (node (ref "U1") (pin "6") (pinfunction "GND_6") (pintype "power_in"))
      (node (ref "VL0_1") (pin "TP") (pinfunction "TP_TP") (pintype "input"))
    )
    (net (code "60") (name "Net-(U1-GPIO1)") (class "Default")
      (node (ref "U1") (pin "7") (pinfunction "GPIO1_7") (pintype "output"))
      (node (ref "VL0_5") (pin "TP") (pinfunction "TP_TP") (pintype "input"))
    )
    (net (code "61") (name "Net-(U1-SCL)") (class "Default")
      (node (ref "U1") (pin "10") (pinfunction "SCL_10") (pintype "open_collector"))
      (node (ref "VL0_3") (pin "TP") (pinfunction "TP_TP") (pintype "input"))
    )
    (net (code "62") (name "Net-(U1-SDA)") (class "Default")
      (node (ref "U1") (pin "9") (pinfunction "SDA_9") (pintype "open_collector"))
      (node (ref "VL0_4") (pin "TP") (pinfunction "TP_TP") (pintype "input"))
    )
    (net (code "63") (name "Net-(U1-XSHUT)") (class "Default")
      (node (ref "U1") (pin "5") (pinfunction "XSHUT_5") (pintype "input"))
      (node (ref "VL0_6") (pin "TP") (pinfunction "TP_TP") (pintype "input"))
    )
    (net (code "64") (name "unconnected-(C_0603-Pad1)") (class "Default")
      (node (ref "C_0603") (pin "1") (pinfunction "1_1") (pintype "passive"))
    )
    (net (code "65") (name "unconnected-(C_0603-Pad2)") (class "Default")
      (node (ref "C_0603") (pin "2") (pinfunction "2_2") (pintype "passive"))
    )
    (net (code "66") (name "unconnected-(IC1B-PA15-Pad38)") (class "Default")
      (node (ref "IC1") (pin "38") (pinfunction "PA15_38") (pintype "bidirectional"))
    )
    (net (code "67") (name "unconnected-(IC1C-PA4-Pad14)") (class "Default")
      (node (ref "IC1") (pin "14") (pinfunction "PA4_14") (pintype "bidirectional"))
    )
    (net (code "68") (name "unconnected-(IC1C-PA5-Pad15)") (class "Default")
      (node (ref "IC1") (pin "15") (pinfunction "PA5_15") (pintype "bidirectional"))
    )
    (net (code "69") (name "unconnected-(IC1F-PC13-Pad2)") (class "Default")
      (node (ref "IC1") (pin "2") (pinfunction "PC13_2") (pintype "bidirectional"))
    )
    (net (code "70") (name "unconnected-(IC1F-PC14-Pad3)") (class "Default")
      (node (ref "IC1") (pin "3") (pinfunction "PC14_3") (pintype "bidirectional"))
    )
    (net (code "71") (name "unconnected-(IC1F-PC15-Pad4)") (class "Default")
      (node (ref "IC1") (pin "4") (pinfunction "PC15_4") (pintype "bidirectional"))
    )
    (net (code "72") (name "unconnected-(R_0603-Pad1)") (class "Default")
      (node (ref "R_0603") (pin "1") (pinfunction "1_1") (pintype "passive"))
    )
    (net (code "73") (name "unconnected-(R_0603-Pad2)") (class "Default")
      (node (ref "R_0603") (pin "2") (pinfunction "2_2") (pintype "passive"))
    )
    (net (code "74") (name "unconnected-(U$2-PadPOWER_1)") (class "Default")
      (node (ref "U$2") (pin "POWER_1") (pinfunction "POWER_1_POWER_1") (pintype "bidirectional"))
    )
    (net (code "75") (name "unconnected-(U$2-PadPOWER_2)") (class "Default")
      (node (ref "U$2") (pin "POWER_2") (pinfunction "POWER_2_POWER_2") (pintype "bidirectional"))
    )
    (net (code "76") (name "unconnected-(U$2-PadPOWER_3)") (class "Default")
      (node (ref "U$2") (pin "POWER_3") (pinfunction "POWER_3_POWER_3") (pintype "bidirectional"))
    )
    (net (code "77") (name "unconnected-(U$2-PadPOWER_4)") (class "Default")
      (node (ref "U$2") (pin "POWER_4") (pinfunction "POWER_4_POWER_4") (pintype "bidirectional"))
    )
    (net (code "78") (name "unconnected-(U$2-PadSIGNAL_1)") (class "Default")
      (node (ref "U$2") (pin "SIGNAL_1") (pinfunction "SIGNAL_1_SIGNAL_1") (pintype "bidirectional"))
    )
    (net (code "79") (name "unconnected-(U$2-PadSIGNAL_2)") (class "Default")
      (node (ref "U$2") (pin "SIGNAL_2") (pinfunction "SIGNAL_2_SIGNAL_2") (pintype "bidirectional"))
    )
    (net (code "80") (name "unconnected-(U$2-PadSIGNAL_3)") (class "Default")
      (node (ref "U$2") (pin "SIGNAL_3") (pinfunction "SIGNAL_3_SIGNAL_3") (pintype "bidirectional"))
    )
    (net (code "81") (name "unconnected-(U$2-PadSIGNAL_4)") (class "Default")
      (node (ref "U$2") (pin "SIGNAL_4") (pinfunction "SIGNAL_4_SIGNAL_4") (pintype "bidirectional"))
    )
    (net (code "82") (name "unconnected-(U1-DNC-Pad8)") (class "Default")
      (node (ref "U1") (pin "8") (pinfunction "DNC_8") (pintype "no_connect"))
    )
  )
)
